# TimerControl.net
KiCad netlist of a schematic drawn in EAGLE
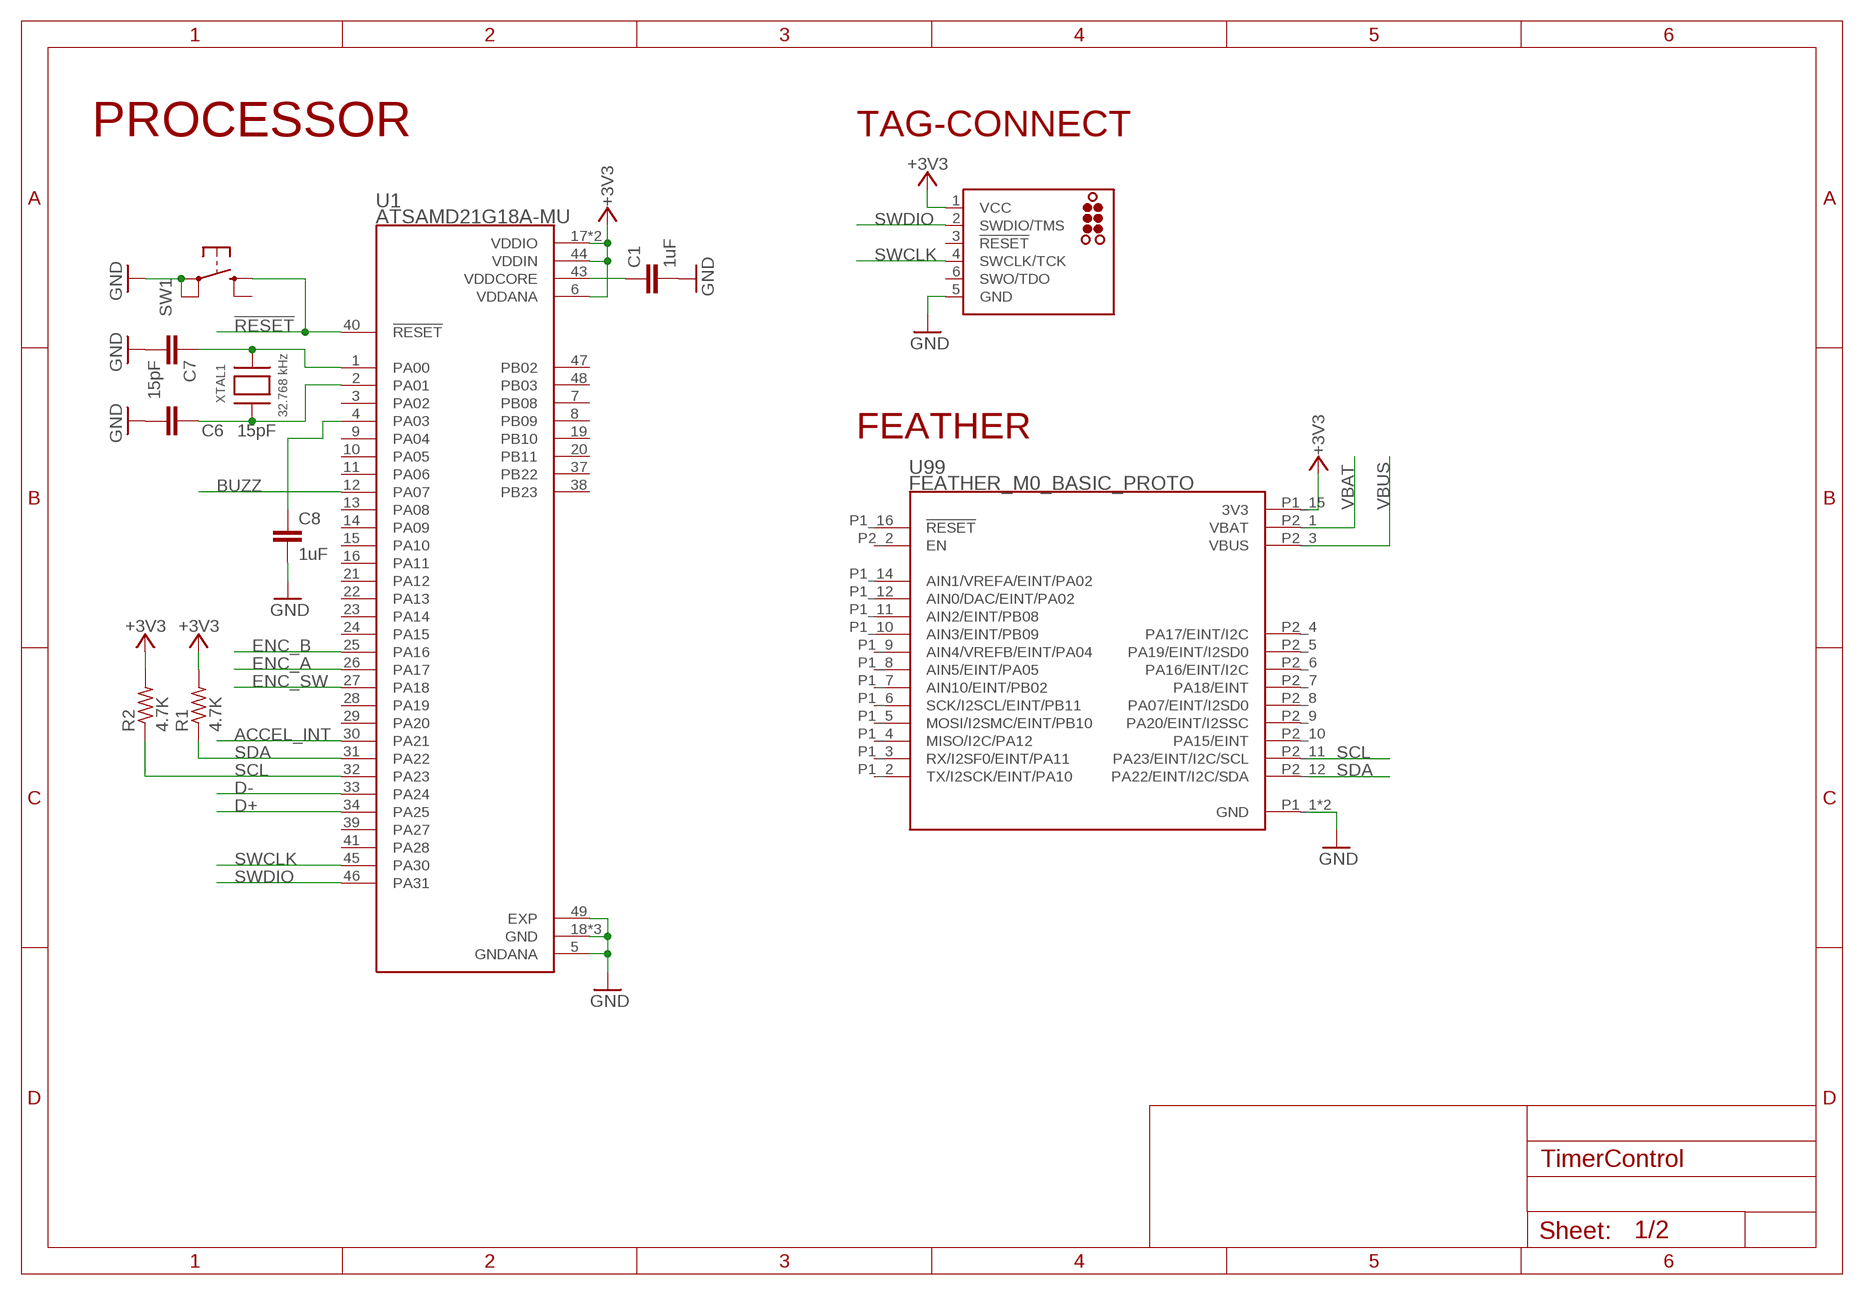
[diagram p0: schematic, sheet 1]
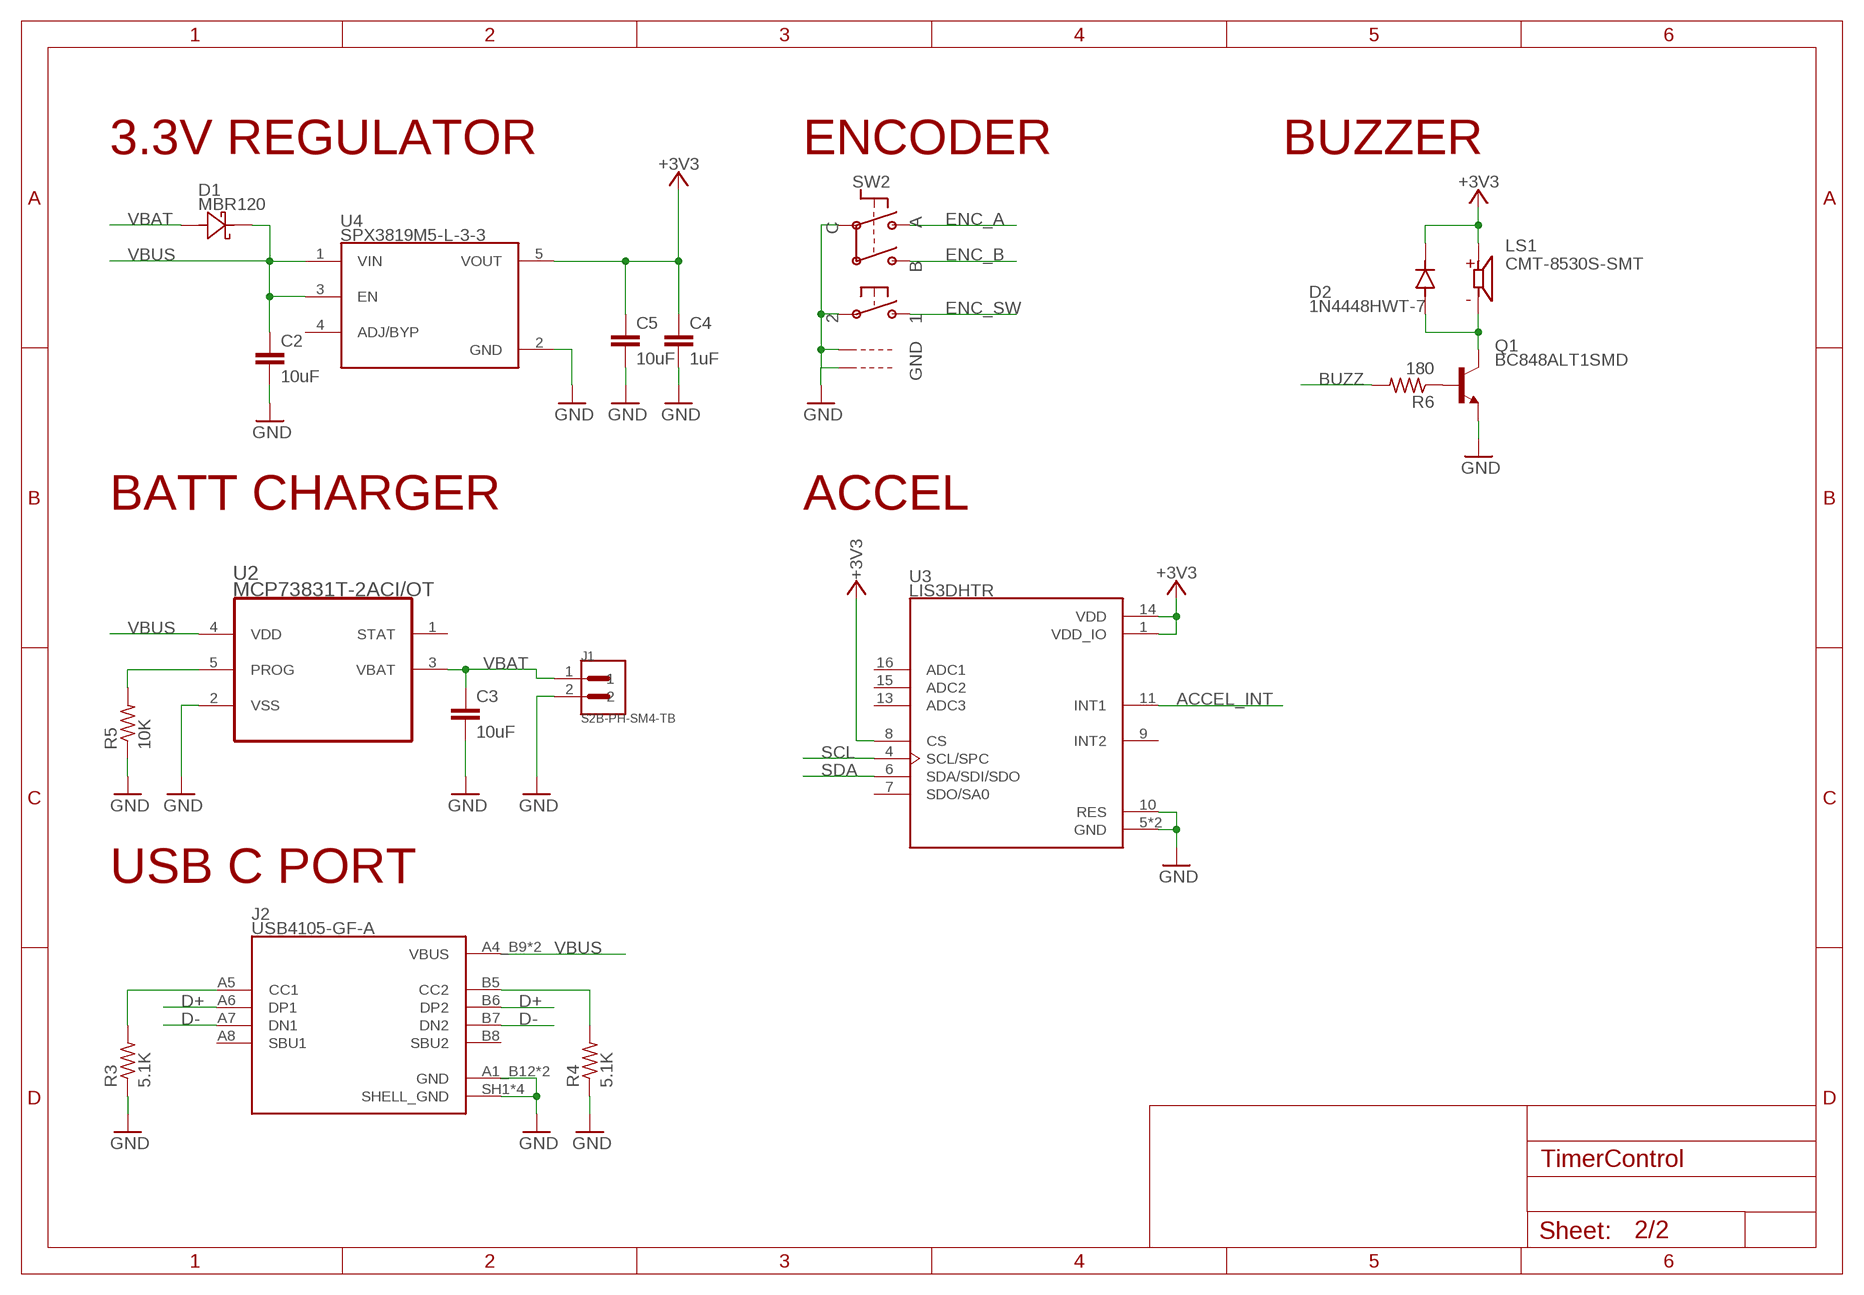
[diagram p1: schematic, sheet 2]

(export (version "E")
  (design (tool "Eeschema 10.0.6"))
  (components
    (comp (ref "C2")
      (value "10uF")
      (footprint "eagle-import:C0603")
      (libsource (lib "eagle-import") (part "C-EUC0603"))
    )
    (comp (ref "C3")
      (value "10uF")
      (footprint "eagle-import:C0603")
      (libsource (lib "eagle-import") (part "C-EUC0603"))
    )
    (comp (ref "C4")
      (value "1uF")
      (footprint "eagle-import:C0603")
      (libsource (lib "eagle-import") (part "C-EUC0603"))
    )
    (comp (ref "C5")
      (value "10uF")
      (footprint "eagle-import:C0603")
      (fields (field (name "REV") "B"))
      (libsource (lib "eagle-import") (part "C-EUC0603"))
    )
    (comp (ref "D1")
      (value "MBR120")
      (footprint "eagle-import:SOD−123FL")
      (libsource (lib "eagle-import") (part "MBR120"))
    )
    (comp (ref "D2")
      (value "1N4448HWT-7")
      (footprint "eagle-import:SODFL1608X65N")
      (fields (field (name "MF") "Diodes Inc."))
      (libsource (lib "eagle-import") (part "1N4448HWT-7"))
    )
    (comp (ref "J1")
      (value "S2B-PH-SM4-TB")
      (footprint "eagle-import:JST_S2B-PH-SM4-TB")
      (fields (field (name "MANUFACTURER") "JST"))
      (libsource (lib "eagle-import") (part "S2B-PH-SM4-TB"))
    )
    (comp (ref "J2")
      (value "USB4105-GF-A")
      (footprint "eagle-import:GCT_USB4105-GF-A")
      (fields (field (name "MANUFACTURER") "Global Connector Technology"))
      (libsource (lib "eagle-import") (part "USB4105-GF-A"))
    )
    (comp (ref "LS1")
      (value "CMT-8530S-SMT")
      (footprint "eagle-import:CUI_CMT-8530S-SMT")
      (fields (field (name "MF") "CUI"))
      (libsource (lib "eagle-import") (part "CMT-8530S-SMT"))
    )
    (comp (ref "Q1")
      (value "BC848ALT1SMD")
      (footprint "eagle-import:SOT23")
      (libsource (lib "eagle-import") (part "BC848SMDALT1"))
    )
    (comp (ref "R3")
      (value "5.1K")
      (footprint "eagle-import:R0603")
      (libsource (lib "eagle-import") (part "R-US_R0603"))
    )
    (comp (ref "R4")
      (value "5.1K")
      (footprint "eagle-import:R0603")
      (libsource (lib "eagle-import") (part "R-US_R0603"))
    )
    (comp (ref "R5")
      (value "10K")
      (footprint "eagle-import:R0603")
      (libsource (lib "eagle-import") (part "R-US_R0603"))
    )
    (comp (ref "R6")
      (value "180")
      (footprint "eagle-import:R0603")
      (libsource (lib "eagle-import") (part "R-US_R0603"))
    )
    (comp (ref "SW2")
      (value "PEC11R_BOURNS_PEC11")
      (footprint "eagle-import:PEC11R")
      (libsource (lib "eagle-import") (part "PEC11R_PEC11_BOURNS"))
    )
    (comp (ref "U2")
      (value "MCP73831T-2ACI/OT")
      (footprint "eagle-import:SOT95P280X145-5N")
      (fields (field (name "DIGIKEY_PART_NUMBER") "MCP73831T-2ACI/OTTR-ND") (field (name "MF") "Microchip"))
      (libsource (lib "eagle-import") (part "MCP73831T-2ACI/OT"))
    )
    (comp (ref "U3")
      (value "LIS3DHTR")
      (footprint "eagle-import:XDCR_LIS3DHTR")
      (fields (field (name "MANUFACTURER") "STMicroelectronics"))
      (libsource (lib "eagle-import") (part "LIS3DHTR"))
    )
    (comp (ref "U4")
      (value "SPX3819M5-L-3-3")
      (footprint "eagle-import:SOT95P280X145-5N")
      (fields (field (name "MF") "MaxLinear"))
      (libsource (lib "eagle-import") (part "SPX3819M5-L-3-3"))
    )
    (comp (ref "C1")
      (value "1uF")
      (footprint "eagle-import:C0603")
      (libsource (lib "eagle-import") (part "C-EUC0603"))
    )
    (comp (ref "C6")
      (value "15pF")
      (footprint "eagle-import:C0603")
      (libsource (lib "eagle-import") (part "C-EUC0603"))
    )
    (comp (ref "C7")
      (value "15pF")
      (footprint "eagle-import:C0603")
      (libsource (lib "eagle-import") (part "C-EUC0603"))
    )
    (comp (ref "C8")
      (value "1uF")
      (footprint "eagle-import:C0603")
      (libsource (lib "eagle-import") (part "C-EUC0603"))
    )
    (comp (ref "J3")
      (value "TC2030_SWD-MCP-NL")
      (footprint "eagle-import:TC2030-MCP-NL")
      (libsource (lib "eagle-import") (part "TC2030_SWD-MCP-NL"))
    )
    (comp (ref "R1")
      (value "4.7K")
      (footprint "eagle-import:R0603")
      (libsource (lib "eagle-import") (part "R-US_R0603"))
    )
    (comp (ref "R2")
      (value "4.7K")
      (footprint "eagle-import:R0603")
      (libsource (lib "eagle-import") (part "R-US_R0603"))
    )
    (comp (ref "SW1")
      (value "KMR2")
      (footprint "eagle-import:2.80X4.60")
      (libsource (lib "eagle-import") (part "4PIN_SMD_BUTTON"))
    )
    (comp (ref "U1")
      (value "ATSAMD21G18A-MU")
      (footprint "eagle-import:QFN50P700X700X90-49N")
      (fields (field (name "MF") "Microchip"))
      (libsource (lib "eagle-import") (part "ATSAMD21G18A-MU"))
    )
    (comp (ref "U99")
      (value "FEATHER_M0_BASIC_PROTO")
      (footprint "eagle-import:MODULE_FEATHER_M0_BASIC_PROTO")
      (fields (field (name "MF") "Adafruit Industries") (field (name "MP") "Feather M0 Basic Proto"))
      (libsource (lib "eagle-import") (part "FEATHER_M0_BASIC_PROTO"))
    )
    (comp (ref "XTAL1")
      (value "32.768 kHz")
      (footprint "eagle-import:XTAL3215")
      (libsource (lib "eagle-import") (part "XTAL"))
    )
  )
  (nets
    (net (code "1") (name "+3V3") (class "Default")
      (node (ref "C4") (pin "1") (pinfunction "1_1") (pintype "passive"))
      (node (ref "C5") (pin "1") (pinfunction "1_1") (pintype "passive"))
      (node (ref "D2") (pin "C") (pinfunction "K_C") (pintype "passive"))
      (node (ref "J3") (pin "1") (pinfunction "VCC_1") (pintype "passive"))
      (node (ref "LS1") (pin "P") (pinfunction "P_P") (pintype "passive"))
      (node (ref "R1") (pin "2") (pinfunction "2_2") (pintype "passive"))
      (node (ref "R2") (pin "2") (pinfunction "2_2") (pintype "passive"))
      (node (ref "U1") (pin "17") (pinfunction "VDDIO_17") (pintype "power_in"))
      (node (ref "U1") (pin "36") (pinfunction "VDDIO_36") (pintype "power_in"))
      (node (ref "U1") (pin "44") (pinfunction "VDDIN_44") (pintype "power_in"))
      (node (ref "U1") (pin "6") (pinfunction "VDDANA_6") (pintype "power_in"))
      (node (ref "U3") (pin "1") (pinfunction "VDD_IO_1") (pintype "power_in"))
      (node (ref "U3") (pin "14") (pinfunction "VDD_14") (pintype "power_in"))
      (node (ref "U3") (pin "8") (pinfunction "CS_8") (pintype "input"))
      (node (ref "U4") (pin "5") (pinfunction "VOUT_5") (pintype "output"))
      (node (ref "U99") (pin "P1_15") (pinfunction "3V3_P1_15") (pintype "power_in"))
    )
    (net (code "2") (name "ACCEL_INT") (class "Default")
      (node (ref "U1") (pin "30") (pinfunction "PA21_30") (pintype "bidirectional"))
      (node (ref "U3") (pin "11") (pinfunction "INT1_11") (pintype "output"))
    )
    (net (code "3") (name "BUZZ") (class "Default")
      (node (ref "R6") (pin "2") (pinfunction "2_2") (pintype "passive"))
      (node (ref "U1") (pin "12") (pinfunction "PA07_12") (pintype "bidirectional"))
    )
    (net (code "4") (name "D+") (class "Default")
      (node (ref "J2") (pin "A6") (pinfunction "DP1_A6") (pintype "bidirectional"))
      (node (ref "J2") (pin "B6") (pinfunction "DP2_B6") (pintype "bidirectional"))
      (node (ref "U1") (pin "34") (pinfunction "PA25_34") (pintype "bidirectional"))
    )
    (net (code "5") (name "D-") (class "Default")
      (node (ref "J2") (pin "A7") (pinfunction "DN1_A7") (pintype "bidirectional"))
      (node (ref "J2") (pin "B7") (pinfunction "DN2_B7") (pintype "bidirectional"))
      (node (ref "U1") (pin "33") (pinfunction "PA24_33") (pintype "bidirectional"))
    )
    (net (code "6") (name "ENC_A") (class "Default")
      (node (ref "SW2") (pin "P$A") (pinfunction "P$A_P$A") (pintype "passive"))
      (node (ref "U1") (pin "26") (pinfunction "PA17_26") (pintype "bidirectional"))
    )
    (net (code "7") (name "ENC_B") (class "Default")
      (node (ref "SW2") (pin "P$B") (pinfunction "P$B_P$B") (pintype "passive"))
      (node (ref "U1") (pin "25") (pinfunction "PA16_25") (pintype "bidirectional"))
    )
    (net (code "8") (name "ENC_SW") (class "Default")
      (node (ref "SW2") (pin "P$1") (pinfunction "P$1_P$1") (pintype "passive"))
      (node (ref "U1") (pin "27") (pinfunction "PA18_27") (pintype "bidirectional"))
    )
    (net (code "9") (name "GND") (class "Default")
      (node (ref "C1") (pin "2") (pinfunction "2_2") (pintype "passive"))
      (node (ref "C2") (pin "2") (pinfunction "2_2") (pintype "passive"))
      (node (ref "C3") (pin "2") (pinfunction "2_2") (pintype "passive"))
      (node (ref "C4") (pin "2") (pinfunction "2_2") (pintype "passive"))
      (node (ref "C5") (pin "2") (pinfunction "2_2") (pintype "passive"))
      (node (ref "C6") (pin "2") (pinfunction "2_2") (pintype "passive"))
      (node (ref "C7") (pin "2") (pinfunction "2_2") (pintype "passive"))
      (node (ref "C8") (pin "2") (pinfunction "2_2") (pintype "passive"))
      (node (ref "J1") (pin "2") (pinfunction "2_2") (pintype "passive"))
      (node (ref "J2") (pin "A1_B12") (pinfunction "GND_A1_B12") (pintype "power_in"))
      (node (ref "J2") (pin "B1_A12") (pinfunction "GND_B1_A12") (pintype "power_in"))
      (node (ref "J2") (pin "SH1") (pinfunction "SHELL_GND_SH1") (pintype "power_in"))
      (node (ref "J2") (pin "SH2") (pinfunction "SHELL_GND_SH2") (pintype "power_in"))
      (node (ref "J2") (pin "SH3") (pinfunction "SHELL_GND_SH3") (pintype "power_in"))
      (node (ref "J2") (pin "SH4") (pinfunction "SHELL_GND_SH4") (pintype "power_in"))
      (node (ref "J3") (pin "5") (pinfunction "GND_5") (pintype "passive"))
      (node (ref "Q1") (pin "2") (pinfunction "E_2") (pintype "passive"))
      (node (ref "R3") (pin "1") (pinfunction "1_1") (pintype "passive"))
      (node (ref "R4") (pin "1") (pinfunction "1_1") (pintype "passive"))
      (node (ref "R5") (pin "1") (pinfunction "1_1") (pintype "passive"))
      (node (ref "SW1") (pin "A") (pinfunction "P_A") (pintype "passive"))
      (node (ref "SW1") (pin "A'") (pinfunction "P1_A'") (pintype "passive"))
      (node (ref "SW2") (pin "P$2") (pinfunction "P$2_P$2") (pintype "passive"))
      (node (ref "SW2") (pin "P$C") (pinfunction "P$C_P$C") (pintype "passive"))
      (node (ref "SW2") (pin "P$GND1") (pinfunction "P$GND1_P$GND1") (pintype "passive"))
      (node (ref "SW2") (pin "P$GND2") (pinfunction "P$GND2_P$GND2") (pintype "passive"))
      (node (ref "U1") (pin "18") (pinfunction "GND_18") (pintype "power_in"))
      (node (ref "U1") (pin "35") (pinfunction "GND_35") (pintype "power_in"))
      (node (ref "U1") (pin "42") (pinfunction "GND_42") (pintype "power_in"))
      (node (ref "U1") (pin "49") (pinfunction "EXP_49") (pintype "power_in"))
      (node (ref "U1") (pin "5") (pinfunction "GNDANA_5") (pintype "power_in"))
      (node (ref "U2") (pin "2") (pinfunction "VSS_2") (pintype "power_in"))
      (node (ref "U3") (pin "10") (pinfunction "RES_10") (pintype "passive"))
      (node (ref "U3") (pin "12") (pinfunction "GND_12") (pintype "power_in"))
      (node (ref "U3") (pin "5") (pinfunction "GND_5") (pintype "power_in"))
      (node (ref "U4") (pin "2") (pinfunction "GND_2") (pintype "passive"))
      (node (ref "U99") (pin "P1_1") (pinfunction "GND_P1_1") (pintype "power_in"))
      (node (ref "U99") (pin "P1_13") (pinfunction "GND_P1_13") (pintype "power_in"))
    )
    (net (code "10") (name "Net-(J2-CC1)") (class "Default")
      (node (ref "J2") (pin "A5") (pinfunction "CC1_A5") (pintype "bidirectional"))
      (node (ref "R3") (pin "2") (pinfunction "2_2") (pintype "passive"))
    )
    (net (code "11") (name "Net-(J2-CC2)") (class "Default")
      (node (ref "J2") (pin "B5") (pinfunction "CC2_B5") (pintype "bidirectional"))
      (node (ref "R4") (pin "2") (pinfunction "2_2") (pintype "passive"))
    )
    (net (code "12") (name "Net-(Q1-B)") (class "Default")
      (node (ref "Q1") (pin "1") (pinfunction "B_1") (pintype "passive"))
      (node (ref "R6") (pin "1") (pinfunction "1_1") (pintype "passive"))
    )
    (net (code "13") (name "Net-(Q1-C)") (class "Default")
      (node (ref "D2") (pin "A") (pinfunction "A_A") (pintype "passive"))
      (node (ref "LS1") (pin "N") (pinfunction "N_N") (pintype "passive"))
      (node (ref "Q1") (pin "3") (pinfunction "C_3") (pintype "passive"))
    )
    (net (code "14") (name "Net-(U1-PA00)") (class "Default")
      (node (ref "C7") (pin "1") (pinfunction "1_1") (pintype "passive"))
      (node (ref "U1") (pin "1") (pinfunction "PA00_1") (pintype "bidirectional"))
      (node (ref "XTAL1") (pin "P$2") (pinfunction "P$2_P$2") (pintype "bidirectional"))
    )
    (net (code "15") (name "Net-(U1-PA01)") (class "Default")
      (node (ref "C6") (pin "1") (pinfunction "1_1") (pintype "passive"))
      (node (ref "U1") (pin "2") (pinfunction "PA01_2") (pintype "bidirectional"))
      (node (ref "XTAL1") (pin "P$1") (pinfunction "P$1_P$1") (pintype "bidirectional"))
    )
    (net (code "16") (name "Net-(U1-PA03)") (class "Default")
      (node (ref "C8") (pin "1") (pinfunction "1_1") (pintype "passive"))
      (node (ref "U1") (pin "4") (pinfunction "PA03_4") (pintype "bidirectional"))
    )
    (net (code "17") (name "Net-(U1-VDDCORE)") (class "Default")
      (node (ref "C1") (pin "1") (pinfunction "1_1") (pintype "passive"))
      (node (ref "U1") (pin "43") (pinfunction "VDDCORE_43") (pintype "power_in"))
    )
    (net (code "18") (name "Net-(U2-PROG)") (class "Default")
      (node (ref "R5") (pin "2") (pinfunction "2_2") (pintype "passive"))
      (node (ref "U2") (pin "5") (pinfunction "PROG_5") (pintype "input"))
    )
    (net (code "19") (name "SCL") (class "Default")
      (node (ref "R2") (pin "1") (pinfunction "1_1") (pintype "passive"))
      (node (ref "U1") (pin "32") (pinfunction "PA23_32") (pintype "bidirectional"))
      (node (ref "U3") (pin "4") (pinfunction "SCL/SPC_4") (pintype "input"))
      (node (ref "U99") (pin "P2_11") (pinfunction "PA23/EINT/I2C/SCL_P2_11") (pintype "bidirectional"))
    )
    (net (code "20") (name "SDA") (class "Default")
      (node (ref "R1") (pin "1") (pinfunction "1_1") (pintype "passive"))
      (node (ref "U1") (pin "31") (pinfunction "PA22_31") (pintype "bidirectional"))
      (node (ref "U3") (pin "6") (pinfunction "SDA/SDI/SDO_6") (pintype "bidirectional"))
      (node (ref "U99") (pin "P2_12") (pinfunction "PA22/EINT/I2C/SDA_P2_12") (pintype "bidirectional"))
    )
    (net (code "21") (name "SWCLK") (class "Default")
      (node (ref "J3") (pin "4") (pinfunction "SWCLK/TCK_4") (pintype "output"))
      (node (ref "U1") (pin "45") (pinfunction "PA30_45") (pintype "bidirectional"))
    )
    (net (code "22") (name "SWDIO") (class "Default")
      (node (ref "J3") (pin "2") (pinfunction "SWDIO/TMS_2") (pintype "bidirectional"))
      (node (ref "U1") (pin "46") (pinfunction "PA31_46") (pintype "bidirectional"))
    )
    (net (code "23") (name "VBAT") (class "Default")
      (node (ref "C3") (pin "1") (pinfunction "1_1") (pintype "passive"))
      (node (ref "D1") (pin "A") (pinfunction "2_A") (pintype "passive"))
      (node (ref "J1") (pin "1") (pinfunction "1_1") (pintype "passive"))
      (node (ref "U2") (pin "3") (pinfunction "VBAT_3") (pintype "output"))
      (node (ref "U99") (pin "P2_1") (pinfunction "VBAT_P2_1") (pintype "power_in"))
    )
    (net (code "24") (name "VBUS") (class "Default")
      (node (ref "C2") (pin "1") (pinfunction "1_1") (pintype "passive"))
      (node (ref "D1") (pin "C") (pinfunction "1_C") (pintype "passive"))
      (node (ref "J2") (pin "A4_B9") (pinfunction "VBUS_A4_B9") (pintype "power_in"))
      (node (ref "J2") (pin "B4_A9") (pinfunction "VBUS_B4_A9") (pintype "power_in"))
      (node (ref "U2") (pin "4") (pinfunction "VDD_4") (pintype "power_in"))
      (node (ref "U4") (pin "1") (pinfunction "VIN_1") (pintype "power_in"))
      (node (ref "U4") (pin "3") (pinfunction "EN_3") (pintype "input"))
      (node (ref "U99") (pin "P2_3") (pinfunction "VBUS_P2_3") (pintype "power_in"))
    )
    (net (code "25") (name "unconnected-(J2-SBU1-PadA8)") (class "Default")
      (node (ref "J2") (pin "A8") (pinfunction "SBU1_A8") (pintype "bidirectional"))
    )
    (net (code "26") (name "unconnected-(J2-SBU2-PadB8)") (class "Default")
      (node (ref "J2") (pin "B8") (pinfunction "SBU2_B8") (pintype "bidirectional"))
    )
    (net (code "27") (name "unconnected-(J3-SWO{slash}TDO-Pad6)") (class "Default")
      (node (ref "J3") (pin "6") (pinfunction "SWO/TDO_6") (pintype "bidirectional"))
    )
    (net (code "28") (name "unconnected-(J3-~{RESET}-Pad3)") (class "Default")
      (node (ref "J3") (pin "3") (pinfunction "~{RESET}_3") (pintype "output"))
    )
    (net (code "29") (name "unconnected-(SW1-S1-PadB')") (class "Default")
      (node (ref "SW1") (pin "B'") (pinfunction "S1_B'") (pintype "passive"))
    )
    (net (code "30") (name "unconnected-(U1-PA02-Pad3)") (class "Default")
      (node (ref "U1") (pin "3") (pinfunction "PA02_3") (pintype "bidirectional"))
    )
    (net (code "31") (name "unconnected-(U1-PA04-Pad9)") (class "Default")
      (node (ref "U1") (pin "9") (pinfunction "PA04_9") (pintype "bidirectional"))
    )
    (net (code "32") (name "unconnected-(U1-PA05-Pad10)") (class "Default")
      (node (ref "U1") (pin "10") (pinfunction "PA05_10") (pintype "bidirectional"))
    )
    (net (code "33") (name "unconnected-(U1-PA06-Pad11)") (class "Default")
      (node (ref "U1") (pin "11") (pinfunction "PA06_11") (pintype "bidirectional"))
    )
    (net (code "34") (name "unconnected-(U1-PA08-Pad13)") (class "Default")
      (node (ref "U1") (pin "13") (pinfunction "PA08_13") (pintype "bidirectional"))
    )
    (net (code "35") (name "unconnected-(U1-PA09-Pad14)") (class "Default")
      (node (ref "U1") (pin "14") (pinfunction "PA09_14") (pintype "bidirectional"))
    )
    (net (code "36") (name "unconnected-(U1-PA10-Pad15)") (class "Default")
      (node (ref "U1") (pin "15") (pinfunction "PA10_15") (pintype "bidirectional"))
    )
    (net (code "37") (name "unconnected-(U1-PA11-Pad16)") (class "Default")
      (node (ref "U1") (pin "16") (pinfunction "PA11_16") (pintype "bidirectional"))
    )
    (net (code "38") (name "unconnected-(U1-PA12-Pad21)") (class "Default")
      (node (ref "U1") (pin "21") (pinfunction "PA12_21") (pintype "bidirectional"))
    )
    (net (code "39") (name "unconnected-(U1-PA13-Pad22)") (class "Default")
      (node (ref "U1") (pin "22") (pinfunction "PA13_22") (pintype "bidirectional"))
    )
    (net (code "40") (name "unconnected-(U1-PA14-Pad23)") (class "Default")
      (node (ref "U1") (pin "23") (pinfunction "PA14_23") (pintype "bidirectional"))
    )
    (net (code "41") (name "unconnected-(U1-PA15-Pad24)") (class "Default")
      (node (ref "U1") (pin "24") (pinfunction "PA15_24") (pintype "bidirectional"))
    )
    (net (code "42") (name "unconnected-(U1-PA19-Pad28)") (class "Default")
      (node (ref "U1") (pin "28") (pinfunction "PA19_28") (pintype "bidirectional"))
    )
    (net (code "43") (name "unconnected-(U1-PA20-Pad29)") (class "Default")
      (node (ref "U1") (pin "29") (pinfunction "PA20_29") (pintype "bidirectional"))
    )
    (net (code "44") (name "unconnected-(U1-PA27-Pad39)") (class "Default")
      (node (ref "U1") (pin "39") (pinfunction "PA27_39") (pintype "bidirectional"))
    )
    (net (code "45") (name "unconnected-(U1-PA28-Pad41)") (class "Default")
      (node (ref "U1") (pin "41") (pinfunction "PA28_41") (pintype "bidirectional"))
    )
    (net (code "46") (name "unconnected-(U1-PB02-Pad47)") (class "Default")
      (node (ref "U1") (pin "47") (pinfunction "PB02_47") (pintype "bidirectional"))
    )
    (net (code "47") (name "unconnected-(U1-PB03-Pad48)") (class "Default")
      (node (ref "U1") (pin "48") (pinfunction "PB03_48") (pintype "bidirectional"))
    )
    (net (code "48") (name "unconnected-(U1-PB08-Pad7)") (class "Default")
      (node (ref "U1") (pin "7") (pinfunction "PB08_7") (pintype "bidirectional"))
    )
    (net (code "49") (name "unconnected-(U1-PB09-Pad8)") (class "Default")
      (node (ref "U1") (pin "8") (pinfunction "PB09_8") (pintype "bidirectional"))
    )
    (net (code "50") (name "unconnected-(U1-PB10-Pad19)") (class "Default")
      (node (ref "U1") (pin "19") (pinfunction "PB10_19") (pintype "bidirectional"))
    )
    (net (code "51") (name "unconnected-(U1-PB11-Pad20)") (class "Default")
      (node (ref "U1") (pin "20") (pinfunction "PB11_20") (pintype "bidirectional"))
    )
    (net (code "52") (name "unconnected-(U1-PB22-Pad37)") (class "Default")
      (node (ref "U1") (pin "37") (pinfunction "PB22_37") (pintype "bidirectional"))
    )
    (net (code "53") (name "unconnected-(U1-PB23-Pad38)") (class "Default")
      (node (ref "U1") (pin "38") (pinfunction "PB23_38") (pintype "bidirectional"))
    )
    (net (code "54") (name "unconnected-(U2-STAT-Pad1)") (class "Default")
      (node (ref "U2") (pin "1") (pinfunction "STAT_1") (pintype "output"))
    )
    (net (code "55") (name "unconnected-(U3-ADC1-Pad16)") (class "Default")
      (node (ref "U3") (pin "16") (pinfunction "ADC1_16") (pintype "input"))
    )
    (net (code "56") (name "unconnected-(U3-ADC2-Pad15)") (class "Default")
      (node (ref "U3") (pin "15") (pinfunction "ADC2_15") (pintype "input"))
    )
    (net (code "57") (name "unconnected-(U3-ADC3-Pad13)") (class "Default")
      (node (ref "U3") (pin "13") (pinfunction "ADC3_13") (pintype "input"))
    )
    (net (code "58") (name "unconnected-(U3-INT2-Pad9)") (class "Default")
      (node (ref "U3") (pin "9") (pinfunction "INT2_9") (pintype "output"))
    )
    (net (code "59") (name "unconnected-(U3-SDO{slash}SA0-Pad7)") (class "Default")
      (node (ref "U3") (pin "7") (pinfunction "SDO/SA0_7") (pintype "bidirectional"))
    )
    (net (code "60") (name "unconnected-(U4-ADJ{slash}BYP-Pad4)") (class "Default")
      (node (ref "U4") (pin "4") (pinfunction "ADJ/BYP_4") (pintype "passive"))
    )
    (net (code "61") (name "unconnected-(U99-AIN0{slash}DAC{slash}EINT{slash}PA02-PadP1_12)") (class "Default")
      (node (ref "U99") (pin "P1_12") (pinfunction "AIN0/DAC/EINT/PA02_P1_12") (pintype "bidirectional"))
    )
    (net (code "62") (name "unconnected-(U99-AIN1{slash}VREFA{slash}EINT{slash}PA02-PadP1_14)") (class "Default")
      (node (ref "U99") (pin "P1_14") (pinfunction "AIN1/VREFA/EINT/PA02_P1_14") (pintype "bidirectional"))
    )
    (net (code "63") (name "unconnected-(U99-AIN2{slash}EINT{slash}PB08-PadP1_11)") (class "Default")
      (node (ref "U99") (pin "P1_11") (pinfunction "AIN2/EINT/PB08_P1_11") (pintype "bidirectional"))
    )
    (net (code "64") (name "unconnected-(U99-AIN3{slash}EINT{slash}PB09-PadP1_10)") (class "Default")
      (node (ref "U99") (pin "P1_10") (pinfunction "AIN3/EINT/PB09_P1_10") (pintype "bidirectional"))
    )
    (net (code "65") (name "unconnected-(U99-AIN4{slash}VREFB{slash}EINT{slash}PA04-PadP1_9)") (class "Default")
      (node (ref "U99") (pin "P1_9") (pinfunction "AIN4/VREFB/EINT/PA04_P1_9") (pintype "bidirectional"))
    )
    (net (code "66") (name "unconnected-(U99-AIN5{slash}EINT{slash}PA05-PadP1_8)") (class "Default")
      (node (ref "U99") (pin "P1_8") (pinfunction "AIN5/EINT/PA05_P1_8") (pintype "bidirectional"))
    )
    (net (code "67") (name "unconnected-(U99-AIN10{slash}EINT{slash}PB02-PadP1_7)") (class "Default")
      (node (ref "U99") (pin "P1_7") (pinfunction "AIN10/EINT/PB02_P1_7") (pintype "bidirectional"))
    )
    (net (code "68") (name "unconnected-(U99-EN-PadP2_2)") (class "Default")
      (node (ref "U99") (pin "P2_2") (pinfunction "EN_P2_2") (pintype "input"))
    )
    (net (code "69") (name "unconnected-(U99-MISO{slash}I2C{slash}PA12-PadP1_4)") (class "Default")
      (node (ref "U99") (pin "P1_4") (pinfunction "MISO/I2C/PA12_P1_4") (pintype "bidirectional"))
    )
    (net (code "70") (name "unconnected-(U99-MOSI{slash}I2SMC{slash}EINT{slash}PB10-PadP1_5)") (class "Default")
      (node (ref "U99") (pin "P1_5") (pinfunction "MOSI/I2SMC/EINT/PB10_P1_5") (pintype "bidirectional"))
    )
    (net (code "71") (name "unconnected-(U99-PA07{slash}EINT{slash}I2SD0-PadP2_8)") (class "Default")
      (node (ref "U99") (pin "P2_8") (pinfunction "PA07/EINT/I2SD0_P2_8") (pintype "bidirectional"))
    )
    (net (code "72") (name "unconnected-(U99-PA15{slash}EINT-PadP2_10)") (class "Default")
      (node (ref "U99") (pin "P2_10") (pinfunction "PA15/EINT_P2_10") (pintype "bidirectional"))
    )
    (net (code "73") (name "unconnected-(U99-PA16{slash}EINT{slash}I2C-PadP2_6)") (class "Default")
      (node (ref "U99") (pin "P2_6") (pinfunction "PA16/EINT/I2C_P2_6") (pintype "bidirectional"))
    )
    (net (code "74") (name "unconnected-(U99-PA17{slash}EINT{slash}I2C-PadP2_4)") (class "Default")
      (node (ref "U99") (pin "P2_4") (pinfunction "PA17/EINT/I2C_P2_4") (pintype "bidirectional"))
    )
    (net (code "75") (name "unconnected-(U99-PA18{slash}EINT-PadP2_7)") (class "Default")
      (node (ref "U99") (pin "P2_7") (pinfunction "PA18/EINT_P2_7") (pintype "bidirectional"))
    )
    (net (code "76") (name "unconnected-(U99-PA19{slash}EINT{slash}I2SD0-PadP2_5)") (class "Default")
      (node (ref "U99") (pin "P2_5") (pinfunction "PA19/EINT/I2SD0_P2_5") (pintype "bidirectional"))
    )
    (net (code "77") (name "unconnected-(U99-PA20{slash}EINT{slash}I2SSC-PadP2_9)") (class "Default")
      (node (ref "U99") (pin "P2_9") (pinfunction "PA20/EINT/I2SSC_P2_9") (pintype "bidirectional"))
    )
    (net (code "78") (name "unconnected-(U99-RX{slash}I2SF0{slash}EINT{slash}PA11-PadP1_3)") (class "Default")
      (node (ref "U99") (pin "P1_3") (pinfunction "RX/I2SF0/EINT/PA11_P1_3") (pintype "bidirectional"))
    )
    (net (code "79") (name "unconnected-(U99-SCK{slash}I2SCL{slash}EINT{slash}PB11-PadP1_6)") (class "Default")
      (node (ref "U99") (pin "P1_6") (pinfunction "SCK/I2SCL/EINT/PB11_P1_6") (pintype "bidirectional"))
    )
    (net (code "80") (name "unconnected-(U99-TX{slash}I2SCK{slash}EINT{slash}PA10-PadP1_2)") (class "Default")
      (node (ref "U99") (pin "P1_2") (pinfunction "TX/I2SCK/EINT/PA10_P1_2") (pintype "bidirectional"))
    )
    (net (code "81") (name "unconnected-(U99-~{RESET}-PadP1_16)") (class "Default")
      (node (ref "U99") (pin "P1_16") (pinfunction "~{RESET}_P1_16") (pintype "input"))
    )
    (net (code "82") (name "~{RESET}") (class "Default")
      (node (ref "SW1") (pin "B") (pinfunction "S_B") (pintype "passive"))
      (node (ref "U1") (pin "40") (pinfunction "~{RESET}_40") (pintype "input"))
    )
  )
)
